# metal_detector_proto1.net
KiCad netlist of a schematic drawn in EAGLE
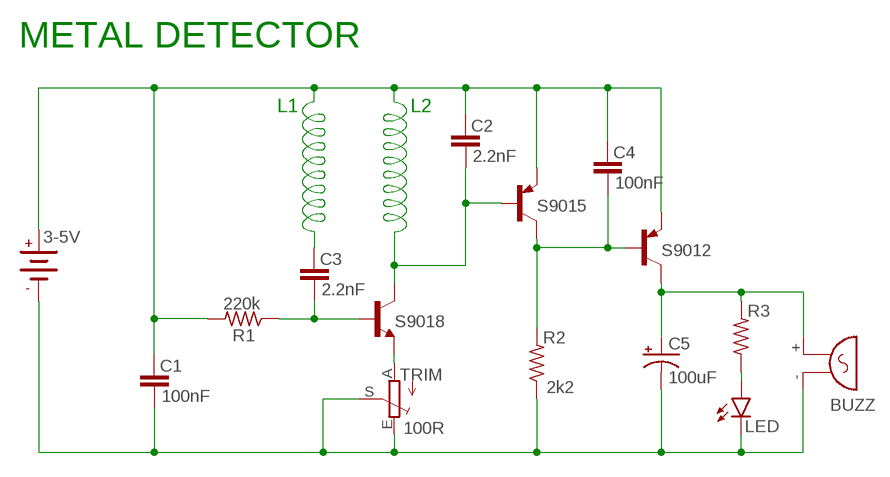
[diagram p0: schematic, sheet 1]

(export (version "E")
  (design (tool "Eeschema 10.0.6"))
  (components
    (comp (ref "3-5V")
      (value "3-5V")
      (footprint "eagle-import:AB9V")
      (libsource (lib "eagle-import") (part "DC_BATT"))
    )
    (comp (ref "BUZZ")
      (value "F/QMX")
      (footprint "eagle-import:F_QMX")
      (libsource (lib "eagle-import") (part "F/QMX"))
    )
    (comp (ref "C1")
      (value "100nF")
      (footprint "eagle-import:BOX_SMALL")
      (libsource (lib "eagle-import") (part "CER/FILMBOX.1"))
    )
    (comp (ref "C2")
      (value "2.2nF")
      (footprint "eagle-import:BOX_SMALL")
      (libsource (lib "eagle-import") (part "CER/FILMBOX.1"))
    )
    (comp (ref "C3")
      (value "2.2nF")
      (footprint "eagle-import:BOX_SMALL")
      (libsource (lib "eagle-import") (part "CER/FILMBOX.1"))
    )
    (comp (ref "C4")
      (value "100nF")
      (footprint "eagle-import:BOX_SMALL")
      (libsource (lib "eagle-import") (part "CER/FILMBOX.1"))
    )
    (comp (ref "C5")
      (value "100uF")
      (footprint "eagle-import:063_025")
      (libsource (lib "eagle-import") (part "0631"))
    )
    (comp (ref "LED")
      (value "LED5MM")
      (footprint "eagle-import:LED5MM")
      (libsource (lib "eagle-import") (part "LED5MM"))
    )
    (comp (ref "R1")
      (value "220k")
      (footprint "eagle-import:R0207_3")
      (libsource (lib "eagle-import") (part "R_.3B"))
    )
    (comp (ref "R2")
      (value "2k2")
      (footprint "eagle-import:R0207_3")
      (libsource (lib "eagle-import") (part "R_.3B"))
    )
    (comp (ref "R3")
      (value "R_.3B")
      (footprint "eagle-import:R0207_3")
      (libsource (lib "eagle-import") (part "R_.3B"))
    )
    (comp (ref "S9012")
      (value "S9012")
      (footprint "eagle-import:TO92-EBC")
      (libsource (lib "eagle-import") (part "S9012"))
    )
    (comp (ref "S9015")
      (value "S9015")
      (footprint "eagle-import:TO92-EBC")
      (libsource (lib "eagle-import") (part "S9015"))
    )
    (comp (ref "S9018")
      (value "S9018")
      (footprint "eagle-import:TO92-EBC")
      (libsource (lib "eagle-import") (part "S9018"))
    )
    (comp (ref "TRIM")
      (value "100R")
      (footprint "eagle-import:RJ9W")
      (libsource (lib "eagle-import") (part "TRIM_EU-RJ9W"))
    )
  )
  (nets
    (net (code "1") (name "/N$7") (class "Default")
      (node (ref "3-5V") (pin "+") (pinfunction "+_+") (pintype "passive"))
      (node (ref "C1") (pin "1") (pinfunction "1_1") (pintype "passive"))
      (node (ref "C2") (pin "1") (pinfunction "1_1") (pintype "passive"))
      (node (ref "C2") (pin "2") (pinfunction "2_2") (pintype "passive"))
      (node (ref "C3") (pin "1") (pinfunction "1_1") (pintype "passive"))
      (node (ref "C4") (pin "1") (pinfunction "1_1") (pintype "passive"))
      (node (ref "R1") (pin "2") (pinfunction "2_2") (pintype "passive"))
      (node (ref "S9012") (pin "1") (pinfunction "E_1") (pintype "passive"))
      (node (ref "S9015") (pin "1") (pinfunction "E_1") (pintype "passive"))
      (node (ref "S9015") (pin "2") (pinfunction "B_2") (pintype "passive"))
      (node (ref "S9018") (pin "3") (pinfunction "C_3") (pintype "passive"))
    )
    (net (code "2") (name "Net-(BUZZ-1)") (class "Default")
      (node (ref "3-5V") (pin "-") (pinfunction "-_-") (pintype "passive"))
      (node (ref "BUZZ") (pin "-") (pinfunction "1_-") (pintype "passive"))
      (node (ref "C1") (pin "2") (pinfunction "2_2") (pintype "passive"))
      (node (ref "C5") (pin "-") (pinfunction "-_-") (pintype "passive"))
      (node (ref "LED") (pin "K") (pinfunction "C_K") (pintype "passive"))
      (node (ref "R2") (pin "1") (pinfunction "1_1") (pintype "passive"))
      (node (ref "TRIM") (pin "E") (pinfunction "E_E") (pintype "passive"))
      (node (ref "TRIM") (pin "S") (pinfunction "S_S") (pintype "passive"))
    )
    (net (code "3") (name "Net-(BUZZ-2)") (class "Default")
      (node (ref "BUZZ") (pin "+") (pinfunction "2_+") (pintype "passive"))
      (node (ref "C5") (pin "+") (pinfunction "+_+") (pintype "passive"))
      (node (ref "R3") (pin "2") (pinfunction "2_2") (pintype "passive"))
      (node (ref "S9012") (pin "3") (pinfunction "C_3") (pintype "passive"))
    )
    (net (code "4") (name "Net-(LED-PadA)") (class "Default")
      (node (ref "LED") (pin "A") (pinfunction "A_A") (pintype "passive"))
      (node (ref "R3") (pin "1") (pinfunction "1_1") (pintype "passive"))
    )
    (net (code "5") (name "Net-(S9012-B)") (class "Default")
      (node (ref "C4") (pin "2") (pinfunction "2_2") (pintype "passive"))
      (node (ref "R2") (pin "2") (pinfunction "2_2") (pintype "passive"))
      (node (ref "S9012") (pin "2") (pinfunction "B_2") (pintype "passive"))
      (node (ref "S9015") (pin "3") (pinfunction "C_3") (pintype "passive"))
    )
    (net (code "6") (name "Net-(S9018-B)") (class "Default")
      (node (ref "C3") (pin "2") (pinfunction "2_2") (pintype "passive"))
      (node (ref "R1") (pin "1") (pinfunction "1_1") (pintype "passive"))
      (node (ref "S9018") (pin "2") (pinfunction "B_2") (pintype "passive"))
    )
    (net (code "7") (name "Net-(S9018-E)") (class "Default")
      (node (ref "S9018") (pin "1") (pinfunction "E_1") (pintype "passive"))
      (node (ref "TRIM") (pin "A") (pinfunction "A_A") (pintype "passive"))
    )
  )
)
